# ADC_Mod_1.net
KiCad netlist of a schematic drawn in Altium Designer
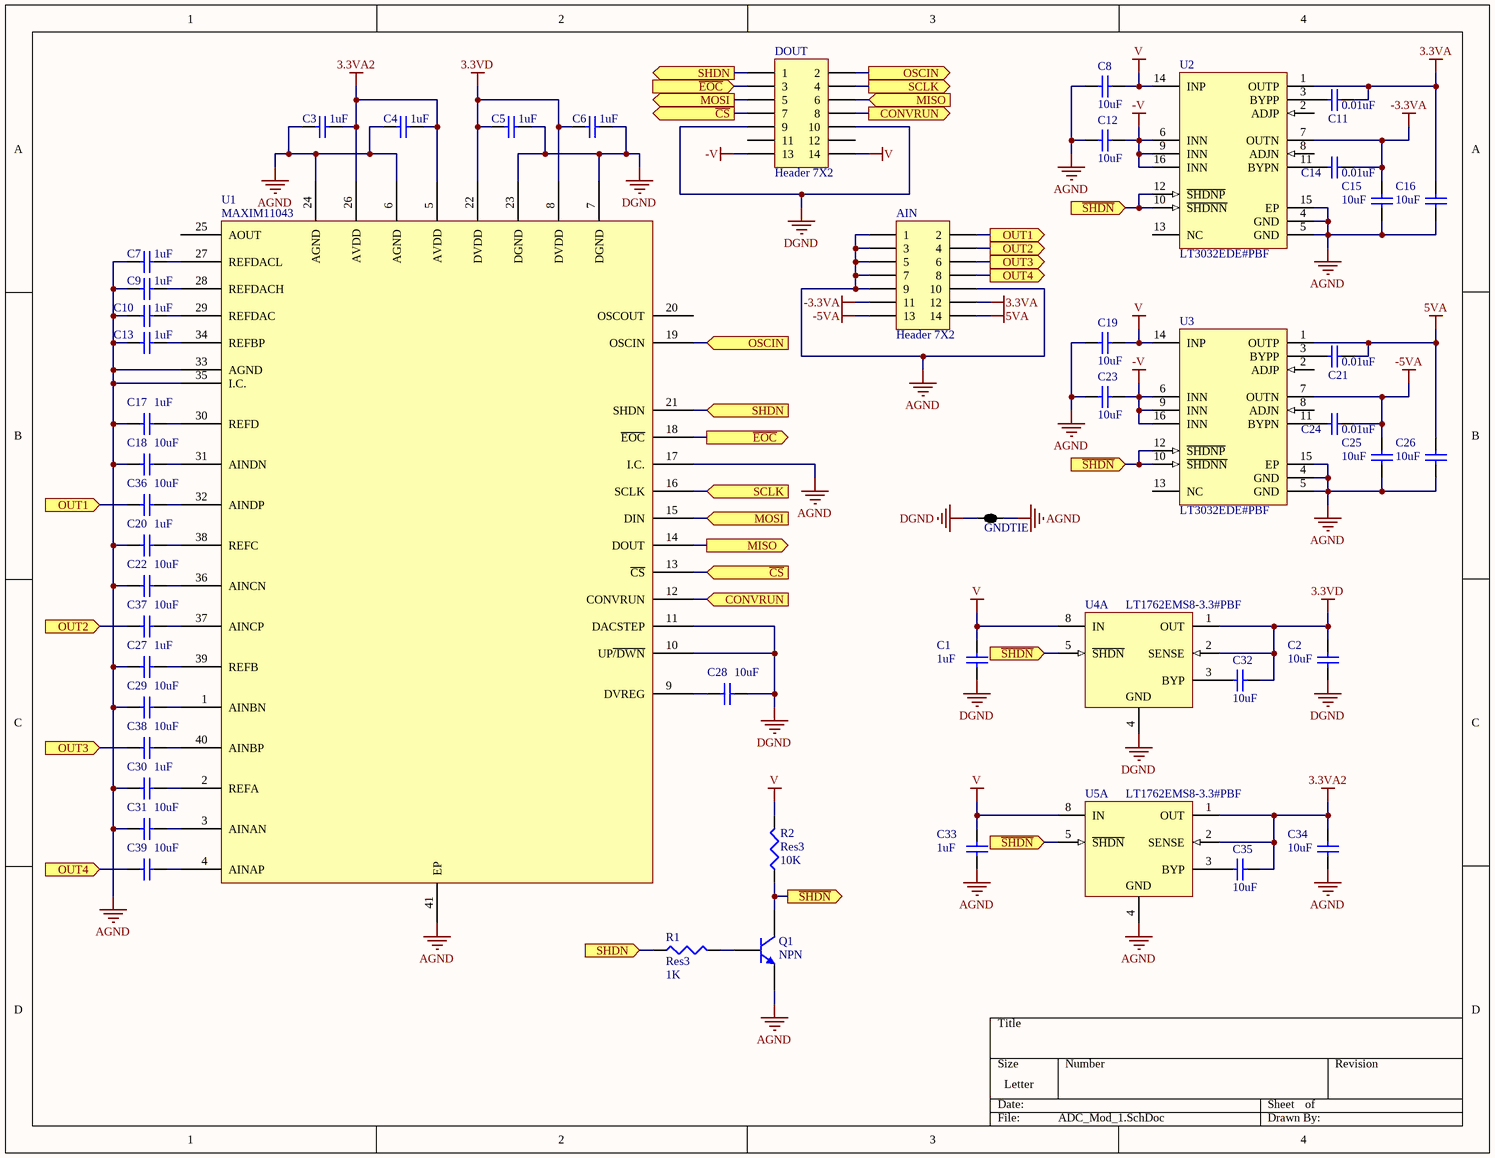
[diagram p0: ADC_Mod_1.SchDoc]

(export (version "E")
  (design (tool "Eeschema 10.0.6"))
  (components
    (comp (ref "AIN")
      (value "Header 7X2")
      (footprint "CLP-107-02-L-DH-TR")
      (description "Header, 7-Pin, Dual row")
      (fields (field (name "PUBLISHER") "Altium Limited"))
      (libsource (lib "Miscellaneous Connectors") (part "Header 7X2"))
    )
    (comp (ref "C1")
      (value "1uF")
      (footprint "0402")
      (description "Capacitor")
      (fields (field (name "Comment") "Cap") (field (name "PUBLISHER") "Altium Limited"))
      (libsource (lib "Miscellaneous Devices") (part "Cap"))
    )
    (comp (ref "C2")
      (value "10uF")
      (footprint "0402")
      (description "Capacitor")
      (fields (field (name "Comment") "Cap") (field (name "PUBLISHER") "Altium Limited"))
      (libsource (lib "Miscellaneous Devices") (part "Cap"))
    )
    (comp (ref "C3")
      (value "1uF")
      (footprint "0402")
      (description "Capacitor")
      (fields (field (name "Comment") "Cap") (field (name "PUBLISHER") "Altium Limited"))
      (libsource (lib "Miscellaneous Devices") (part "Cap"))
    )
    (comp (ref "C4")
      (value "1uF")
      (footprint "0402")
      (description "Capacitor")
      (fields (field (name "Comment") "Cap") (field (name "PUBLISHER") "Altium Limited"))
      (libsource (lib "Miscellaneous Devices") (part "Cap"))
    )
    (comp (ref "C5")
      (value "1uF")
      (footprint "0402")
      (description "Capacitor")
      (fields (field (name "Comment") "Cap") (field (name "PUBLISHER") "Altium Limited"))
      (libsource (lib "Miscellaneous Devices") (part "Cap"))
    )
    (comp (ref "C6")
      (value "1uF")
      (footprint "0402")
      (description "Capacitor")
      (fields (field (name "Comment") "Cap") (field (name "PUBLISHER") "Altium Limited"))
      (libsource (lib "Miscellaneous Devices") (part "Cap"))
    )
    (comp (ref "C7")
      (value "1uF")
      (footprint "0402")
      (description "Capacitor")
      (fields (field (name "Comment") "Cap") (field (name "PUBLISHER") "Altium Limited"))
      (libsource (lib "Miscellaneous Devices") (part "Cap"))
    )
    (comp (ref "C8")
      (value "10uF")
      (footprint "0402")
      (description "Capacitor")
      (fields (field (name "Comment") "Cap") (field (name "PUBLISHER") "Altium Limited"))
      (libsource (lib "Miscellaneous Devices") (part "Cap"))
    )
    (comp (ref "C9")
      (value "1uF")
      (footprint "0402")
      (description "Capacitor")
      (fields (field (name "Comment") "Cap") (field (name "PUBLISHER") "Altium Limited"))
      (libsource (lib "Miscellaneous Devices") (part "Cap"))
    )
    (comp (ref "C10")
      (value "1uF")
      (footprint "0402")
      (description "Capacitor")
      (fields (field (name "Comment") "Cap") (field (name "PUBLISHER") "Altium Limited"))
      (libsource (lib "Miscellaneous Devices") (part "Cap"))
    )
    (comp (ref "C11")
      (value "0.01uF")
      (footprint "0402")
      (description "Capacitor")
      (fields (field (name "Comment") "Cap") (field (name "PUBLISHER") "Altium Limited"))
      (libsource (lib "Miscellaneous Devices") (part "Cap"))
    )
    (comp (ref "C12")
      (value "10uF")
      (footprint "0402")
      (description "Capacitor")
      (fields (field (name "Comment") "Cap") (field (name "PUBLISHER") "Altium Limited"))
      (libsource (lib "Miscellaneous Devices") (part "Cap"))
    )
    (comp (ref "C13")
      (value "1uF")
      (footprint "0402")
      (description "Capacitor")
      (fields (field (name "Comment") "Cap") (field (name "PUBLISHER") "Altium Limited"))
      (libsource (lib "Miscellaneous Devices") (part "Cap"))
    )
    (comp (ref "C14")
      (value "0.01uF")
      (footprint "0402")
      (description "Capacitor")
      (fields (field (name "Comment") "Cap") (field (name "PUBLISHER") "Altium Limited"))
      (libsource (lib "Miscellaneous Devices") (part "Cap"))
    )
    (comp (ref "C15")
      (value "10uF")
      (footprint "0402")
      (description "Capacitor")
      (fields (field (name "Comment") "Cap") (field (name "PUBLISHER") "Altium Limited"))
      (libsource (lib "Miscellaneous Devices") (part "Cap"))
    )
    (comp (ref "C16")
      (value "10uF")
      (footprint "0402")
      (description "Capacitor")
      (fields (field (name "Comment") "Cap") (field (name "PUBLISHER") "Altium Limited"))
      (libsource (lib "Miscellaneous Devices") (part "Cap"))
    )
    (comp (ref "C17")
      (value "1uF")
      (footprint "0402")
      (description "Capacitor")
      (fields (field (name "Comment") "Cap") (field (name "PUBLISHER") "Altium Limited"))
      (libsource (lib "Miscellaneous Devices") (part "Cap"))
    )
    (comp (ref "C18")
      (value "10uF")
      (footprint "0402")
      (description "Capacitor")
      (fields (field (name "Comment") "Cap") (field (name "PUBLISHER") "Altium Limited"))
      (libsource (lib "Miscellaneous Devices") (part "Cap"))
    )
    (comp (ref "C19")
      (value "10uF")
      (footprint "0402")
      (description "Capacitor")
      (fields (field (name "Comment") "Cap") (field (name "PUBLISHER") "Altium Limited"))
      (libsource (lib "Miscellaneous Devices") (part "Cap"))
    )
    (comp (ref "C20")
      (value "1uF")
      (footprint "0402")
      (description "Capacitor")
      (fields (field (name "Comment") "Cap") (field (name "PUBLISHER") "Altium Limited"))
      (libsource (lib "Miscellaneous Devices") (part "Cap"))
    )
    (comp (ref "C21")
      (value "0.01uF")
      (footprint "0402")
      (description "Capacitor")
      (fields (field (name "Comment") "Cap") (field (name "PUBLISHER") "Altium Limited"))
      (libsource (lib "Miscellaneous Devices") (part "Cap"))
    )
    (comp (ref "C22")
      (value "10uF")
      (footprint "0402")
      (description "Capacitor")
      (fields (field (name "Comment") "Cap") (field (name "PUBLISHER") "Altium Limited"))
      (libsource (lib "Miscellaneous Devices") (part "Cap"))
    )
    (comp (ref "C23")
      (value "10uF")
      (footprint "0402")
      (description "Capacitor")
      (fields (field (name "Comment") "Cap") (field (name "PUBLISHER") "Altium Limited"))
      (libsource (lib "Miscellaneous Devices") (part "Cap"))
    )
    (comp (ref "C24")
      (value "0.01uF")
      (footprint "0402")
      (description "Capacitor")
      (fields (field (name "Comment") "Cap") (field (name "PUBLISHER") "Altium Limited"))
      (libsource (lib "Miscellaneous Devices") (part "Cap"))
    )
    (comp (ref "C25")
      (value "10uF")
      (footprint "0402")
      (description "Capacitor")
      (fields (field (name "Comment") "Cap") (field (name "PUBLISHER") "Altium Limited"))
      (libsource (lib "Miscellaneous Devices") (part "Cap"))
    )
    (comp (ref "C26")
      (value "10uF")
      (footprint "0402")
      (description "Capacitor")
      (fields (field (name "Comment") "Cap") (field (name "PUBLISHER") "Altium Limited"))
      (libsource (lib "Miscellaneous Devices") (part "Cap"))
    )
    (comp (ref "C27")
      (value "1uF")
      (footprint "0402")
      (description "Capacitor")
      (fields (field (name "Comment") "Cap") (field (name "PUBLISHER") "Altium Limited"))
      (libsource (lib "Miscellaneous Devices") (part "Cap"))
    )
    (comp (ref "C28")
      (value "10uF")
      (footprint "0402")
      (description "Capacitor")
      (fields (field (name "Comment") "Cap") (field (name "PUBLISHER") "Altium Limited"))
      (libsource (lib "Miscellaneous Devices") (part "Cap"))
    )
    (comp (ref "C29")
      (value "10uF")
      (footprint "0402")
      (description "Capacitor")
      (fields (field (name "Comment") "Cap") (field (name "PUBLISHER") "Altium Limited"))
      (libsource (lib "Miscellaneous Devices") (part "Cap"))
    )
    (comp (ref "C30")
      (value "1uF")
      (footprint "0402")
      (description "Capacitor")
      (fields (field (name "Comment") "Cap") (field (name "PUBLISHER") "Altium Limited"))
      (libsource (lib "Miscellaneous Devices") (part "Cap"))
    )
    (comp (ref "C31")
      (value "10uF")
      (footprint "0402")
      (description "Capacitor")
      (fields (field (name "Comment") "Cap") (field (name "PUBLISHER") "Altium Limited"))
      (libsource (lib "Miscellaneous Devices") (part "Cap"))
    )
    (comp (ref "C32")
      (value "10uF")
      (footprint "0402")
      (description "Capacitor")
      (fields (field (name "Comment") "Cap") (field (name "PUBLISHER") "Altium Limited"))
      (libsource (lib "Miscellaneous Devices") (part "Cap"))
    )
    (comp (ref "C33")
      (value "1uF")
      (footprint "0402")
      (description "Capacitor")
      (fields (field (name "Comment") "Cap") (field (name "PUBLISHER") "Altium Limited"))
      (libsource (lib "Miscellaneous Devices") (part "Cap"))
    )
    (comp (ref "C34")
      (value "10uF")
      (footprint "0402")
      (description "Capacitor")
      (fields (field (name "Comment") "Cap") (field (name "PUBLISHER") "Altium Limited"))
      (libsource (lib "Miscellaneous Devices") (part "Cap"))
    )
    (comp (ref "C35")
      (value "10uF")
      (footprint "0402")
      (description "Capacitor")
      (fields (field (name "Comment") "Cap") (field (name "PUBLISHER") "Altium Limited"))
      (libsource (lib "Miscellaneous Devices") (part "Cap"))
    )
    (comp (ref "C36")
      (value "10uF")
      (footprint "0402")
      (description "Capacitor")
      (fields (field (name "Comment") "Cap") (field (name "PUBLISHER") "Altium Limited"))
      (libsource (lib "Miscellaneous Devices") (part "Cap"))
    )
    (comp (ref "C37")
      (value "10uF")
      (footprint "0402")
      (description "Capacitor")
      (fields (field (name "Comment") "Cap") (field (name "PUBLISHER") "Altium Limited"))
      (libsource (lib "Miscellaneous Devices") (part "Cap"))
    )
    (comp (ref "C38")
      (value "10uF")
      (footprint "0402")
      (description "Capacitor")
      (fields (field (name "Comment") "Cap") (field (name "PUBLISHER") "Altium Limited"))
      (libsource (lib "Miscellaneous Devices") (part "Cap"))
    )
    (comp (ref "C39")
      (value "10uF")
      (footprint "0402")
      (description "Capacitor")
      (fields (field (name "Comment") "Cap") (field (name "PUBLISHER") "Altium Limited"))
      (libsource (lib "Miscellaneous Devices") (part "Cap"))
    )
    (comp (ref "DOUT")
      (value "Header 7X2")
      (footprint "FTSH-107-01-L-DH")
      (description "Header, 7-Pin, Dual row")
      (fields (field (name "PUBLISHER") "Altium Limited"))
      (libsource (lib "Miscellaneous Connectors") (part "Header 7X2"))
    )
    (comp (ref "GNDTIE")
      (value "2 way net tie junction")
      (footprint "2way_LP")
      (libsource (lib "NetTieLib") (part "2way"))
    )
    (comp (ref "Q1")
      (value "NPN")
      (footprint "SOT23_L")
      (description "NPN Bipolar Transistor")
      (fields (field (name "PUBLISHER") "Altium Limited"))
      (libsource (lib "Miscellaneous Devices") (part "NPN"))
    )
    (comp (ref "R1")
      (value "Res3")
      (footprint "J1-0603")
      (description "Resistor")
      (fields (field (name "ALTIUM_VALUE") "1K") (field (name "PUBLISHER") "Altium Limited"))
      (libsource (lib "Miscellaneous Devices") (part "Res3"))
    )
    (comp (ref "R2")
      (value "Res3")
      (footprint "J1-0603")
      (description "Resistor")
      (fields (field (name "ALTIUM_VALUE") "10K") (field (name "PUBLISHER") "Altium Limited"))
      (libsource (lib "Miscellaneous Devices") (part "Res3"))
    )
    (comp (ref "U1")
      (value "MAXIM11043")
      (footprint "QFN50P600X600X80_HS-41N")
      (libsource (lib "MAXIM11043") (part "MAXIM11043"))
    )
    (comp (ref "U2")
      (value "LT3032EDE#PBF")
      (footprint "LT-DE14MA-14_V")
      (fields (field (name "MANUFACTURER") "Linear Technology"))
      (libsource (lib "Linear Technology Power Management LDO Linear Regulators") (part "LT3032EDE#PBF"))
    )
    (comp (ref "U3")
      (value "LT3032EDE#PBF")
      (footprint "LT-DE14MA-14_V")
      (fields (field (name "MANUFACTURER") "Linear Technology"))
      (libsource (lib "Linear Technology Power Management LDO Linear Regulators") (part "LT3032EDE#PBF"))
    )
    (comp (ref "U4")
      (value "LT1762EMS8-3.3#PBF")
      (footprint "LT-MS8_N")
      (fields (field (name "MANUFACTURER") "Linear Technology"))
      (libsource (lib "Linear Technology Power Management LDO Linear Regulators") (part "LT1762EMS8-3.3#PBF"))
    )
    (comp (ref "U5")
      (value "LT1762EMS8-3.3#PBF")
      (footprint "LT-MS8_N")
      (fields (field (name "MANUFACTURER") "Linear Technology"))
      (libsource (lib "Linear Technology Power Management LDO Linear Regulators") (part "LT1762EMS8-3.3#PBF"))
    )
  )
  (nets
    (net (code "1") (name "-3.3VA") (class "Default")
      (node (ref "AIN") (pin "11") (pinfunction "11_11") (pintype "passive"))
      (node (ref "C14") (pin "2") (pinfunction "2_2") (pintype "passive"))
      (node (ref "C15") (pin "2") (pinfunction "2_2") (pintype "passive"))
      (node (ref "U2") (pin "7") (pinfunction "OUTN_7") (pintype "power_in"))
    )
    (net (code "2") (name "-5VA") (class "Default")
      (node (ref "AIN") (pin "13") (pinfunction "13_13") (pintype "passive"))
      (node (ref "C24") (pin "2") (pinfunction "2_2") (pintype "passive"))
      (node (ref "C25") (pin "2") (pinfunction "2_2") (pintype "passive"))
      (node (ref "U3") (pin "7") (pinfunction "OUTN_7") (pintype "power_in"))
    )
    (net (code "3") (name "-V") (class "Default")
      (node (ref "C12") (pin "1") (pinfunction "1_1") (pintype "passive"))
      (node (ref "C23") (pin "1") (pinfunction "1_1") (pintype "passive"))
      (node (ref "DOUT") (pin "13") (pinfunction "13_13") (pintype "passive"))
      (node (ref "U2") (pin "16") (pinfunction "INN_16") (pintype "power_in"))
      (node (ref "U2") (pin "6") (pinfunction "INN_6") (pintype "power_in"))
      (node (ref "U2") (pin "9") (pinfunction "INN_9") (pintype "power_in"))
      (node (ref "U3") (pin "16") (pinfunction "INN_16") (pintype "power_in"))
      (node (ref "U3") (pin "6") (pinfunction "INN_6") (pintype "power_in"))
      (node (ref "U3") (pin "9") (pinfunction "INN_9") (pintype "power_in"))
    )
    (net (code "4") (name "/CONVRUN") (class "Default")
      (node (ref "DOUT") (pin "8") (pinfunction "8_8") (pintype "passive"))
      (node (ref "U1") (pin "12") (pinfunction "CONVRUN_12") (pintype "passive"))
    )
    (net (code "5") (name "/MISO") (class "Default")
      (node (ref "DOUT") (pin "6") (pinfunction "6_6") (pintype "passive"))
      (node (ref "U1") (pin "14") (pinfunction "DOUT_14") (pintype "passive"))
    )
    (net (code "6") (name "/MOSI") (class "Default")
      (node (ref "DOUT") (pin "5") (pinfunction "5_5") (pintype "passive"))
      (node (ref "U1") (pin "15") (pinfunction "DIN_15") (pintype "passive"))
    )
    (net (code "7") (name "/OSCIN") (class "Default")
      (node (ref "DOUT") (pin "2") (pinfunction "2_2") (pintype "passive"))
      (node (ref "U1") (pin "19") (pinfunction "OSCIN_19") (pintype "passive"))
    )
    (net (code "8") (name "/OUT1") (class "Default")
      (node (ref "AIN") (pin "2") (pinfunction "2_2") (pintype "passive"))
      (node (ref "C36") (pin "1") (pinfunction "1_1") (pintype "passive"))
    )
    (net (code "9") (name "/OUT2") (class "Default")
      (node (ref "AIN") (pin "4") (pinfunction "4_4") (pintype "passive"))
      (node (ref "C37") (pin "1") (pinfunction "1_1") (pintype "passive"))
    )
    (net (code "10") (name "/OUT3") (class "Default")
      (node (ref "AIN") (pin "6") (pinfunction "6_6") (pintype "passive"))
      (node (ref "C38") (pin "1") (pinfunction "1_1") (pintype "passive"))
    )
    (net (code "11") (name "/OUT4") (class "Default")
      (node (ref "AIN") (pin "8") (pinfunction "8_8") (pintype "passive"))
      (node (ref "C39") (pin "1") (pinfunction "1_1") (pintype "passive"))
    )
    (net (code "12") (name "/SCLK") (class "Default")
      (node (ref "DOUT") (pin "4") (pinfunction "4_4") (pintype "passive"))
      (node (ref "U1") (pin "16") (pinfunction "SCLK_16") (pintype "passive"))
    )
    (net (code "13") (name "/SHDN") (class "Default")
      (node (ref "DOUT") (pin "1") (pinfunction "1_1") (pintype "passive"))
      (node (ref "R1") (pin "1") (pinfunction "1_1") (pintype "passive"))
      (node (ref "U1") (pin "21") (pinfunction "SHDN_21") (pintype "passive"))
    )
    (net (code "14") (name "/~{CS}") (class "Default")
      (node (ref "DOUT") (pin "7") (pinfunction "7_7") (pintype "passive"))
      (node (ref "U1") (pin "13") (pinfunction "~{CS}_13") (pintype "passive"))
    )
    (net (code "15") (name "/~{EOC}") (class "Default")
      (node (ref "DOUT") (pin "3") (pinfunction "3_3") (pintype "passive"))
      (node (ref "U1") (pin "18") (pinfunction "~{EOC}_18") (pintype "passive"))
    )
    (net (code "16") (name "/~{SHDN}") (class "Default")
      (node (ref "Q1") (pin "1") (pinfunction "C_1") (pintype "passive"))
      (node (ref "R2") (pin "1") (pinfunction "1_1") (pintype "passive"))
      (node (ref "U2") (pin "10") (pinfunction "~{SHDNN}_10") (pintype "input"))
      (node (ref "U2") (pin "12") (pinfunction "~{SHDNP}_12") (pintype "input"))
      (node (ref "U3") (pin "10") (pinfunction "~{SHDNN}_10") (pintype "input"))
      (node (ref "U3") (pin "12") (pinfunction "~{SHDNP}_12") (pintype "input"))
      (node (ref "U4") (pin "5") (pinfunction "~{SHDN}_5") (pintype "input"))
      (node (ref "U5") (pin "5") (pinfunction "~{SHDN}_5") (pintype "input"))
    )
    (net (code "17") (name "3.3VA") (class "Default")
      (node (ref "AIN") (pin "12") (pinfunction "12_12") (pintype "passive"))
      (node (ref "C11") (pin "2") (pinfunction "2_2") (pintype "passive"))
      (node (ref "C16") (pin "2") (pinfunction "2_2") (pintype "passive"))
      (node (ref "U2") (pin "1") (pinfunction "OUTP_1") (pintype "power_in"))
    )
    (net (code "18") (name "3.3VA2") (class "Default")
      (node (ref "C3") (pin "2") (pinfunction "2_2") (pintype "passive"))
      (node (ref "C34") (pin "2") (pinfunction "2_2") (pintype "passive"))
      (node (ref "C35") (pin "1") (pinfunction "1_1") (pintype "passive"))
      (node (ref "C4") (pin "2") (pinfunction "2_2") (pintype "passive"))
      (node (ref "U1") (pin "26") (pinfunction "AVDD_26") (pintype "passive"))
      (node (ref "U1") (pin "5") (pinfunction "AVDD_5") (pintype "passive"))
      (node (ref "U5") (pin "1") (pinfunction "OUT_1") (pintype "power_in"))
      (node (ref "U5") (pin "2") (pinfunction "SENSE_2") (pintype "input"))
    )
    (net (code "19") (name "3.3VD") (class "Default")
      (node (ref "C2") (pin "2") (pinfunction "2_2") (pintype "passive"))
      (node (ref "C32") (pin "1") (pinfunction "1_1") (pintype "passive"))
      (node (ref "C5") (pin "1") (pinfunction "1_1") (pintype "passive"))
      (node (ref "C6") (pin "1") (pinfunction "1_1") (pintype "passive"))
      (node (ref "U1") (pin "22") (pinfunction "DVDD_22") (pintype "passive"))
      (node (ref "U1") (pin "8") (pinfunction "DVDD_8") (pintype "passive"))
      (node (ref "U4") (pin "1") (pinfunction "OUT_1") (pintype "power_in"))
      (node (ref "U4") (pin "2") (pinfunction "SENSE_2") (pintype "input"))
    )
    (net (code "20") (name "5VA") (class "Default")
      (node (ref "AIN") (pin "14") (pinfunction "14_14") (pintype "passive"))
      (node (ref "C21") (pin "2") (pinfunction "2_2") (pintype "passive"))
      (node (ref "C26") (pin "2") (pinfunction "2_2") (pintype "passive"))
      (node (ref "U3") (pin "1") (pinfunction "OUTP_1") (pintype "power_in"))
    )
    (net (code "21") (name "AGND") (class "Default")
      (node (ref "AIN") (pin "1") (pinfunction "1_1") (pintype "passive"))
      (node (ref "AIN") (pin "10") (pinfunction "10_10") (pintype "passive"))
      (node (ref "AIN") (pin "3") (pinfunction "3_3") (pintype "passive"))
      (node (ref "AIN") (pin "5") (pinfunction "5_5") (pintype "passive"))
      (node (ref "AIN") (pin "7") (pinfunction "7_7") (pintype "passive"))
      (node (ref "AIN") (pin "9") (pinfunction "9_9") (pintype "passive"))
      (node (ref "C10") (pin "1") (pinfunction "1_1") (pintype "passive"))
      (node (ref "C12") (pin "2") (pinfunction "2_2") (pintype "passive"))
      (node (ref "C13") (pin "1") (pinfunction "1_1") (pintype "passive"))
      (node (ref "C15") (pin "1") (pinfunction "1_1") (pintype "passive"))
      (node (ref "C16") (pin "1") (pinfunction "1_1") (pintype "passive"))
      (node (ref "C17") (pin "1") (pinfunction "1_1") (pintype "passive"))
      (node (ref "C18") (pin "1") (pinfunction "1_1") (pintype "passive"))
      (node (ref "C19") (pin "2") (pinfunction "2_2") (pintype "passive"))
      (node (ref "C20") (pin "1") (pinfunction "1_1") (pintype "passive"))
      (node (ref "C22") (pin "1") (pinfunction "1_1") (pintype "passive"))
      (node (ref "C23") (pin "2") (pinfunction "2_2") (pintype "passive"))
      (node (ref "C25") (pin "1") (pinfunction "1_1") (pintype "passive"))
      (node (ref "C26") (pin "1") (pinfunction "1_1") (pintype "passive"))
      (node (ref "C27") (pin "1") (pinfunction "1_1") (pintype "passive"))
      (node (ref "C29") (pin "1") (pinfunction "1_1") (pintype "passive"))
      (node (ref "C3") (pin "1") (pinfunction "1_1") (pintype "passive"))
      (node (ref "C30") (pin "1") (pinfunction "1_1") (pintype "passive"))
      (node (ref "C31") (pin "1") (pinfunction "1_1") (pintype "passive"))
      (node (ref "C33") (pin "1") (pinfunction "1_1") (pintype "passive"))
      (node (ref "C34") (pin "1") (pinfunction "1_1") (pintype "passive"))
      (node (ref "C4") (pin "1") (pinfunction "1_1") (pintype "passive"))
      (node (ref "C7") (pin "1") (pinfunction "1_1") (pintype "passive"))
      (node (ref "C8") (pin "2") (pinfunction "2_2") (pintype "passive"))
      (node (ref "C9") (pin "1") (pinfunction "1_1") (pintype "passive"))
      (node (ref "GNDTIE") (pin "2") (pinfunction "2_2") (pintype "passive"))
      (node (ref "Q1") (pin "3") (pinfunction "E_3") (pintype "passive"))
      (node (ref "U1") (pin "17") (pinfunction "I.C._17") (pintype "passive"))
      (node (ref "U1") (pin "24") (pinfunction "AGND_24") (pintype "passive"))
      (node (ref "U1") (pin "33") (pinfunction "AGND_33") (pintype "passive"))
      (node (ref "U1") (pin "35") (pinfunction "I.C._35") (pintype "passive"))
      (node (ref "U1") (pin "41") (pinfunction "EP_41") (pintype "passive"))
      (node (ref "U1") (pin "6") (pinfunction "AGND_6") (pintype "passive"))
      (node (ref "U2") (pin "15") (pinfunction "EP_15") (pintype "power_in"))
      (node (ref "U2") (pin "4") (pinfunction "GND_4") (pintype "power_in"))
      (node (ref "U2") (pin "5") (pinfunction "GND_5") (pintype "power_in"))
      (node (ref "U3") (pin "15") (pinfunction "EP_15") (pintype "power_in"))
      (node (ref "U3") (pin "4") (pinfunction "GND_4") (pintype "power_in"))
      (node (ref "U3") (pin "5") (pinfunction "GND_5") (pintype "power_in"))
      (node (ref "U5") (pin "4") (pinfunction "GND_4") (pintype "power_in"))
    )
    (net (code "22") (name "DGND") (class "Default")
      (node (ref "C1") (pin "1") (pinfunction "1_1") (pintype "passive"))
      (node (ref "C2") (pin "1") (pinfunction "1_1") (pintype "passive"))
      (node (ref "C28") (pin "2") (pinfunction "2_2") (pintype "passive"))
      (node (ref "C5") (pin "2") (pinfunction "2_2") (pintype "passive"))
      (node (ref "C6") (pin "2") (pinfunction "2_2") (pintype "passive"))
      (node (ref "DOUT") (pin "10") (pinfunction "10_10") (pintype "passive"))
      (node (ref "DOUT") (pin "9") (pinfunction "9_9") (pintype "passive"))
      (node (ref "GNDTIE") (pin "1") (pinfunction "1_1") (pintype "passive"))
      (node (ref "U1") (pin "10") (pinfunction "UP~{/DWN}_10") (pintype "passive"))
      (node (ref "U1") (pin "11") (pinfunction "DACSTEP_11") (pintype "passive"))
      (node (ref "U1") (pin "23") (pinfunction "DGND_23") (pintype "passive"))
      (node (ref "U1") (pin "7") (pinfunction "DGND_7") (pintype "passive"))
      (node (ref "U4") (pin "4") (pinfunction "GND_4") (pintype "power_in"))
    )
    (net (code "23") (name "Net-(Q1-B)") (class "Default")
      (node (ref "Q1") (pin "2") (pinfunction "B_2") (pintype "passive"))
      (node (ref "R1") (pin "2") (pinfunction "2_2") (pintype "passive"))
    )
    (net (code "24") (name "Net-(U1-AINAN)") (class "Default")
      (node (ref "C31") (pin "2") (pinfunction "2_2") (pintype "passive"))
      (node (ref "U1") (pin "3") (pinfunction "AINAN_3") (pintype "passive"))
    )
    (net (code "25") (name "Net-(U1-AINAP)") (class "Default")
      (node (ref "C39") (pin "2") (pinfunction "2_2") (pintype "passive"))
      (node (ref "U1") (pin "4") (pinfunction "AINAP_4") (pintype "passive"))
    )
    (net (code "26") (name "Net-(U1-AINBN)") (class "Default")
      (node (ref "C29") (pin "2") (pinfunction "2_2") (pintype "passive"))
      (node (ref "U1") (pin "1") (pinfunction "AINBN_1") (pintype "passive"))
    )
    (net (code "27") (name "Net-(U1-AINBP)") (class "Default")
      (node (ref "C38") (pin "2") (pinfunction "2_2") (pintype "passive"))
      (node (ref "U1") (pin "40") (pinfunction "AINBP_40") (pintype "passive"))
    )
    (net (code "28") (name "Net-(U1-AINCN)") (class "Default")
      (node (ref "C22") (pin "2") (pinfunction "2_2") (pintype "passive"))
      (node (ref "U1") (pin "36") (pinfunction "AINCN_36") (pintype "passive"))
    )
    (net (code "29") (name "Net-(U1-AINCP)") (class "Default")
      (node (ref "C37") (pin "2") (pinfunction "2_2") (pintype "passive"))
      (node (ref "U1") (pin "37") (pinfunction "AINCP_37") (pintype "passive"))
    )
    (net (code "30") (name "Net-(U1-AINDN)") (class "Default")
      (node (ref "C18") (pin "2") (pinfunction "2_2") (pintype "passive"))
      (node (ref "U1") (pin "31") (pinfunction "AINDN_31") (pintype "passive"))
    )
    (net (code "31") (name "Net-(U1-AINDP)") (class "Default")
      (node (ref "C36") (pin "2") (pinfunction "2_2") (pintype "passive"))
      (node (ref "U1") (pin "32") (pinfunction "AINDP_32") (pintype "passive"))
    )
    (net (code "32") (name "Net-(U1-DVREG)") (class "Default")
      (node (ref "C28") (pin "1") (pinfunction "1_1") (pintype "passive"))
      (node (ref "U1") (pin "9") (pinfunction "DVREG_9") (pintype "passive"))
    )
    (net (code "33") (name "Net-(U1-REFA)") (class "Default")
      (node (ref "C30") (pin "2") (pinfunction "2_2") (pintype "passive"))
      (node (ref "U1") (pin "2") (pinfunction "REFA_2") (pintype "passive"))
    )
    (net (code "34") (name "Net-(U1-REFB)") (class "Default")
      (node (ref "C27") (pin "2") (pinfunction "2_2") (pintype "passive"))
      (node (ref "U1") (pin "39") (pinfunction "REFB_39") (pintype "passive"))
    )
    (net (code "35") (name "Net-(U1-REFBP)") (class "Default")
      (node (ref "C13") (pin "2") (pinfunction "2_2") (pintype "passive"))
      (node (ref "U1") (pin "34") (pinfunction "REFBP_34") (pintype "passive"))
    )
    (net (code "36") (name "Net-(U1-REFC)") (class "Default")
      (node (ref "C20") (pin "2") (pinfunction "2_2") (pintype "passive"))
      (node (ref "U1") (pin "38") (pinfunction "REFC_38") (pintype "passive"))
    )
    (net (code "37") (name "Net-(U1-REFD)") (class "Default")
      (node (ref "C17") (pin "2") (pinfunction "2_2") (pintype "passive"))
      (node (ref "U1") (pin "30") (pinfunction "REFD_30") (pintype "passive"))
    )
    (net (code "38") (name "Net-(U1-REFDAC)") (class "Default")
      (node (ref "C10") (pin "2") (pinfunction "2_2") (pintype "passive"))
      (node (ref "U1") (pin "29") (pinfunction "REFDAC_29") (pintype "passive"))
    )
    (net (code "39") (name "Net-(U1-REFDACH)") (class "Default")
      (node (ref "C9") (pin "2") (pinfunction "2_2") (pintype "passive"))
      (node (ref "U1") (pin "28") (pinfunction "REFDACH_28") (pintype "passive"))
    )
    (net (code "40") (name "Net-(U1-REFDACL)") (class "Default")
      (node (ref "C7") (pin "2") (pinfunction "2_2") (pintype "passive"))
      (node (ref "U1") (pin "27") (pinfunction "REFDACL_27") (pintype "passive"))
    )
    (net (code "41") (name "Net-(U2-BYPN)") (class "Default")
      (node (ref "C14") (pin "1") (pinfunction "1_1") (pintype "passive"))
      (node (ref "U2") (pin "11") (pinfunction "BYPN_11") (pintype "passive"))
    )
    (net (code "42") (name "Net-(U2-BYPP)") (class "Default")
      (node (ref "C11") (pin "1") (pinfunction "1_1") (pintype "passive"))
      (node (ref "U2") (pin "3") (pinfunction "BYPP_3") (pintype "passive"))
    )
    (net (code "43") (name "Net-(U3-BYPN)") (class "Default")
      (node (ref "C24") (pin "1") (pinfunction "1_1") (pintype "passive"))
      (node (ref "U3") (pin "11") (pinfunction "BYPN_11") (pintype "passive"))
    )
    (net (code "44") (name "Net-(U3-BYPP)") (class "Default")
      (node (ref "C21") (pin "1") (pinfunction "1_1") (pintype "passive"))
      (node (ref "U3") (pin "3") (pinfunction "BYPP_3") (pintype "passive"))
    )
    (net (code "45") (name "Net-(U4A-BYP)") (class "Default")
      (node (ref "C32") (pin "2") (pinfunction "2_2") (pintype "passive"))
      (node (ref "U4") (pin "3") (pinfunction "BYP_3") (pintype "passive"))
    )
    (net (code "46") (name "Net-(U5A-BYP)") (class "Default")
      (node (ref "C35") (pin "2") (pinfunction "2_2") (pintype "passive"))
      (node (ref "U5") (pin "3") (pinfunction "BYP_3") (pintype "passive"))
    )
    (net (code "47") (name "V") (class "Default")
      (node (ref "C1") (pin "2") (pinfunction "2_2") (pintype "passive"))
      (node (ref "C19") (pin "1") (pinfunction "1_1") (pintype "passive"))
      (node (ref "C33") (pin "2") (pinfunction "2_2") (pintype "passive"))
      (node (ref "C8") (pin "1") (pinfunction "1_1") (pintype "passive"))
      (node (ref "DOUT") (pin "14") (pinfunction "14_14") (pintype "passive"))
      (node (ref "R2") (pin "2") (pinfunction "2_2") (pintype "passive"))
      (node (ref "U2") (pin "14") (pinfunction "INP_14") (pintype "power_in"))
      (node (ref "U3") (pin "14") (pinfunction "INP_14") (pintype "power_in"))
      (node (ref "U4") (pin "8") (pinfunction "IN_8") (pintype "power_in"))
      (node (ref "U5") (pin "8") (pinfunction "IN_8") (pintype "power_in"))
    )
    (net (code "48") (name "unconnected-(DOUT-Pad11)") (class "Default")
      (node (ref "DOUT") (pin "11") (pinfunction "11_11") (pintype "passive"))
    )
    (net (code "49") (name "unconnected-(DOUT-Pad12)") (class "Default")
      (node (ref "DOUT") (pin "12") (pinfunction "12_12") (pintype "passive"))
    )
    (net (code "50") (name "unconnected-(U1-AOUT-Pad25)") (class "Default")
      (node (ref "U1") (pin "25") (pinfunction "AOUT_25") (pintype "passive"))
    )
    (net (code "51") (name "unconnected-(U1-OSCOUT-Pad20)") (class "Default")
      (node (ref "U1") (pin "20") (pinfunction "OSCOUT_20") (pintype "passive"))
    )
    (net (code "52") (name "unconnected-(U2-ADJN-Pad8)") (class "Default")
      (node (ref "U2") (pin "8") (pinfunction "ADJN_8") (pintype "input"))
    )
    (net (code "53") (name "unconnected-(U2-ADJP-Pad2)") (class "Default")
      (node (ref "U2") (pin "2") (pinfunction "ADJP_2") (pintype "input"))
    )
    (net (code "54") (name "unconnected-(U2-NC-Pad13)") (class "Default")
      (node (ref "U2") (pin "13") (pinfunction "NC_13") (pintype "passive"))
    )
    (net (code "55") (name "unconnected-(U3-ADJN-Pad8)") (class "Default")
      (node (ref "U3") (pin "8") (pinfunction "ADJN_8") (pintype "input"))
    )
    (net (code "56") (name "unconnected-(U3-ADJP-Pad2)") (class "Default")
      (node (ref "U3") (pin "2") (pinfunction "ADJP_2") (pintype "input"))
    )
    (net (code "57") (name "unconnected-(U3-NC-Pad13)") (class "Default")
      (node (ref "U3") (pin "13") (pinfunction "NC_13") (pintype "passive"))
    )
  )
)
